# Smart_Garden.net
KiCad netlist of a schematic drawn in EAGLE
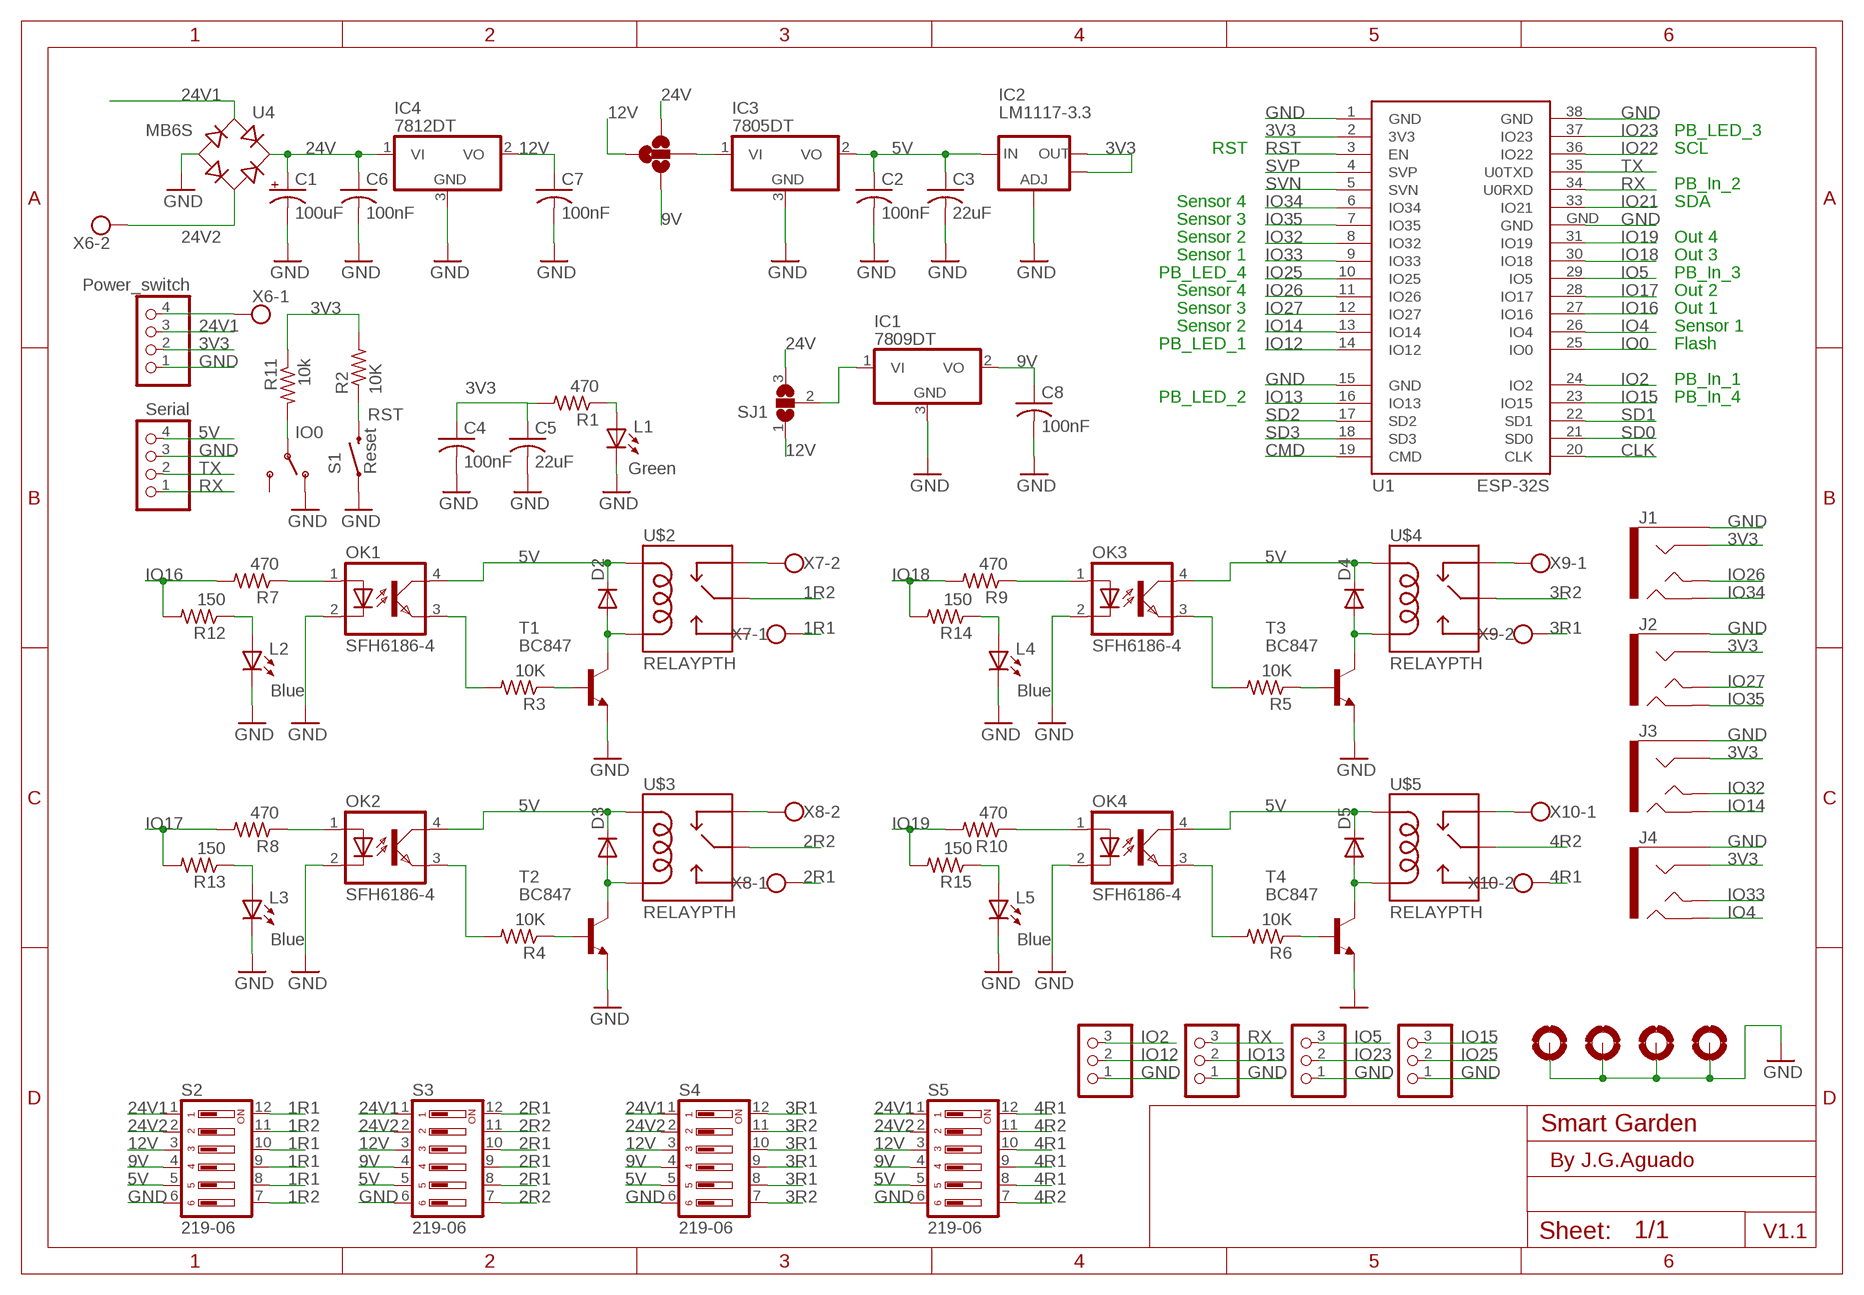
[diagram p0: schematic, sheet 1]

(export (version "E")
  (design (tool "Eeschema 10.0.6"))
  (components
    (comp (ref "C1")
      (value "100uF")
      (footprint "eagle-import:D_7343-31R")
      (libsource (lib "eagle-import") (part "CPOL-USD/7343-31R"))
    )
    (comp (ref "C2")
      (value "100nF")
      (footprint "eagle-import:1206")
      (libsource (lib "eagle-import") (part "C1206"))
    )
    (comp (ref "C3")
      (value "22uF")
      (footprint "eagle-import:1206")
      (libsource (lib "eagle-import") (part "C1206"))
    )
    (comp (ref "C4")
      (value "100nF")
      (footprint "eagle-import:1206")
      (libsource (lib "eagle-import") (part "C1206"))
    )
    (comp (ref "C5")
      (value "22uF")
      (footprint "eagle-import:1206")
      (libsource (lib "eagle-import") (part "C1206"))
    )
    (comp (ref "C6")
      (value "100nF")
      (footprint "eagle-import:1206")
      (libsource (lib "eagle-import") (part "C1206"))
    )
    (comp (ref "C7")
      (value "100nF")
      (footprint "eagle-import:1206")
      (libsource (lib "eagle-import") (part "C1206"))
    )
    (comp (ref "C8")
      (value "100nF")
      (footprint "eagle-import:1206")
      (libsource (lib "eagle-import") (part "C1206"))
    )
    (comp (ref "D2")
      (value "DIODE-SOD123")
      (footprint "eagle-import:SOD123")
      (libsource (lib "eagle-import") (part "DIODE-SOD123"))
    )
    (comp (ref "D3")
      (value "DIODE-SOD123")
      (footprint "eagle-import:SOD123")
      (libsource (lib "eagle-import") (part "DIODE-SOD123"))
    )
    (comp (ref "D4")
      (value "DIODE-SOD123")
      (footprint "eagle-import:SOD123")
      (libsource (lib "eagle-import") (part "DIODE-SOD123"))
    )
    (comp (ref "D5")
      (value "DIODE-SOD123")
      (footprint "eagle-import:SOD123")
      (libsource (lib "eagle-import") (part "DIODE-SOD123"))
    )
    (comp (ref "H1")
      (value "MOUNT-PAD-ROUND3.0")
      (footprint "eagle-import:3,0-PAD")
      (libsource (lib "eagle-import") (part "MOUNT-PAD-ROUND3.0"))
    )
    (comp (ref "H2")
      (value "MOUNT-PAD-ROUND3.0")
      (footprint "eagle-import:3,0-PAD")
      (libsource (lib "eagle-import") (part "MOUNT-PAD-ROUND3.0"))
    )
    (comp (ref "H3")
      (value "MOUNT-PAD-ROUND3.0")
      (footprint "eagle-import:3,0-PAD")
      (libsource (lib "eagle-import") (part "MOUNT-PAD-ROUND3.0"))
    )
    (comp (ref "H4")
      (value "MOUNT-PAD-ROUND3.0")
      (footprint "eagle-import:3,0-PAD")
      (libsource (lib "eagle-import") (part "MOUNT-PAD-ROUND3.0"))
    )
    (comp (ref "IC1")
      (value "7809DT")
      (footprint "eagle-import:TO252")
      (libsource (lib "eagle-import") (part "linear_78DT05"))
    )
    (comp (ref "IC2")
      (value "LM1117-3.3")
      (footprint "eagle-import:SOT223")
      (libsource (lib "eagle-import") (part "V_REG_LM1117SOT223"))
    )
    (comp (ref "IC3")
      (value "7805DT")
      (footprint "eagle-import:TO252")
      (libsource (lib "eagle-import") (part "linear_78DT05"))
    )
    (comp (ref "IC4")
      (value "7812DT")
      (footprint "eagle-import:TO252")
      (libsource (lib "eagle-import") (part "78DT12"))
    )
    (comp (ref "J1")
      (value "AUDIO_JACK_TRRSSMD_RA")
      (footprint "eagle-import:AUDIO_JACK_3.5MM_TRRS_SMD_RA")
      (libsource (lib "eagle-import") (part "AUDIO_JACK_TRRSSMD_RA"))
    )
    (comp (ref "J2")
      (value "AUDIO_JACK_TRRSSMD_RA")
      (footprint "eagle-import:AUDIO_JACK_3.5MM_TRRS_SMD_RA")
      (libsource (lib "eagle-import") (part "AUDIO_JACK_TRRSSMD_RA"))
    )
    (comp (ref "J3")
      (value "AUDIO_JACK_TRRSSMD_RA")
      (footprint "eagle-import:AUDIO_JACK_3.5MM_TRRS_SMD_RA")
      (libsource (lib "eagle-import") (part "AUDIO_JACK_TRRSSMD_RA"))
    )
    (comp (ref "J4")
      (value "AUDIO_JACK_TRRSSMD_RA")
      (footprint "eagle-import:AUDIO_JACK_3.5MM_TRRS_SMD_RA")
      (libsource (lib "eagle-import") (part "AUDIO_JACK_TRRSSMD_RA"))
    )
    (comp (ref "JP1")
      (value "Serial")
      (footprint "eagle-import:1X04")
      (libsource (lib "eagle-import") (part "PINHD-1X4"))
    )
    (comp (ref "JP2")
      (value "PINHD-1X3")
      (footprint "eagle-import:1X03")
      (libsource (lib "eagle-import") (part "PINHD-1X3"))
    )
    (comp (ref "JP3")
      (value "PINHD-1X3")
      (footprint "eagle-import:1X03")
      (libsource (lib "eagle-import") (part "PINHD-1X3"))
    )
    (comp (ref "JP4")
      (value "PINHD-1X3")
      (footprint "eagle-import:1X03")
      (libsource (lib "eagle-import") (part "PINHD-1X3"))
    )
    (comp (ref "JP5")
      (value "PINHD-1X3")
      (footprint "eagle-import:1X03")
      (libsource (lib "eagle-import") (part "PINHD-1X3"))
    )
    (comp (ref "JP6")
      (value "Power_switch")
      (footprint "eagle-import:1X04")
      (libsource (lib "eagle-import") (part "PINHD-1X4"))
    )
    (comp (ref "L1")
      (value "Green")
      (footprint "eagle-import:LED1206")
      (libsource (lib "eagle-import") (part "LED1206"))
    )
    (comp (ref "L2")
      (value "Blue")
      (footprint "eagle-import:LED1206")
      (libsource (lib "eagle-import") (part "LED1206"))
    )
    (comp (ref "L3")
      (value "Blue")
      (footprint "eagle-import:LED1206")
      (libsource (lib "eagle-import") (part "LED1206"))
    )
    (comp (ref "L4")
      (value "Blue")
      (footprint "eagle-import:LED1206")
      (libsource (lib "eagle-import") (part "LED1206"))
    )
    (comp (ref "L5")
      (value "Blue")
      (footprint "eagle-import:LED1206")
      (libsource (lib "eagle-import") (part "LED1206"))
    )
    (comp (ref "OK1")
      (value "SFH6186-4")
      (footprint "eagle-import:SMD4-7")
      (fields (field (name "MF") "VISHAY/TELEFUNKEN"))
      (libsource (lib "eagle-import") (part "SFH618?6-4"))
    )
    (comp (ref "OK2")
      (value "SFH6186-4")
      (footprint "eagle-import:SMD4-7")
      (fields (field (name "MF") "VISHAY/TELEFUNKEN"))
      (libsource (lib "eagle-import") (part "SFH618?6-4"))
    )
    (comp (ref "OK3")
      (value "SFH6186-4")
      (footprint "eagle-import:SMD4-7")
      (fields (field (name "MF") "VISHAY/TELEFUNKEN"))
      (libsource (lib "eagle-import") (part "SFH618?6-4"))
    )
    (comp (ref "OK4")
      (value "SFH6186-4")
      (footprint "eagle-import:SMD4-7")
      (fields (field (name "MF") "VISHAY/TELEFUNKEN"))
      (libsource (lib "eagle-import") (part "SFH618?6-4"))
    )
    (comp (ref "R1")
      (value "470")
      (footprint "eagle-import:1206")
      (libsource (lib "eagle-import") (part "R1206"))
    )
    (comp (ref "R2")
      (value "10K")
      (footprint "eagle-import:R1206")
      (libsource (lib "eagle-import") (part "R-US_R1206"))
    )
    (comp (ref "R3")
      (value "10K")
      (footprint "eagle-import:R1206")
      (libsource (lib "eagle-import") (part "R-US_R1206"))
    )
    (comp (ref "R4")
      (value "10K")
      (footprint "eagle-import:R1206")
      (libsource (lib "eagle-import") (part "R-US_R1206"))
    )
    (comp (ref "R5")
      (value "10K")
      (footprint "eagle-import:R1206")
      (libsource (lib "eagle-import") (part "R-US_R1206"))
    )
    (comp (ref "R6")
      (value "10K")
      (footprint "eagle-import:R1206")
      (libsource (lib "eagle-import") (part "R-US_R1206"))
    )
    (comp (ref "R7")
      (value "470")
      (footprint "eagle-import:R1206")
      (libsource (lib "eagle-import") (part "R-US_R1206"))
    )
    (comp (ref "R8")
      (value "470")
      (footprint "eagle-import:R1206")
      (libsource (lib "eagle-import") (part "R-US_R1206"))
    )
    (comp (ref "R9")
      (value "470")
      (footprint "eagle-import:R1206")
      (libsource (lib "eagle-import") (part "R-US_R1206"))
    )
    (comp (ref "R10")
      (value "470")
      (footprint "eagle-import:R1206")
      (libsource (lib "eagle-import") (part "R-US_R1206"))
    )
    (comp (ref "R11")
      (value "10k")
      (footprint "eagle-import:1206")
      (libsource (lib "eagle-import") (part "R1206"))
    )
    (comp (ref "R12")
      (value "150")
      (footprint "eagle-import:1206")
      (libsource (lib "eagle-import") (part "R1206"))
    )
    (comp (ref "R13")
      (value "150")
      (footprint "eagle-import:1206")
      (libsource (lib "eagle-import") (part "R1206"))
    )
    (comp (ref "R14")
      (value "150")
      (footprint "eagle-import:1206")
      (libsource (lib "eagle-import") (part "R1206"))
    )
    (comp (ref "R15")
      (value "150")
      (footprint "eagle-import:1206")
      (libsource (lib "eagle-import") (part "R1206"))
    )
    (comp (ref "S1")
      (value "Reset")
      (footprint "eagle-import:TACTILE_SWITCH_TALL")
      (libsource (lib "eagle-import") (part "SWITCH-MOMENTARY-2SMD-4"))
    )
    (comp (ref "S2")
      (value "219-06")
      (footprint "eagle-import:CTS-219-06")
      (libsource (lib "eagle-import") (part "219-06"))
    )
    (comp (ref "S3")
      (value "219-06")
      (footprint "eagle-import:CTS-219-06")
      (libsource (lib "eagle-import") (part "219-06"))
    )
    (comp (ref "S4")
      (value "219-06")
      (footprint "eagle-import:CTS-219-06")
      (libsource (lib "eagle-import") (part "219-06"))
    )
    (comp (ref "S5")
      (value "219-06")
      (footprint "eagle-import:CTS-219-06")
      (libsource (lib "eagle-import") (part "219-06"))
    )
    (comp (ref "SJ1")
      (value "SJ2W")
      (footprint "eagle-import:SJ_2")
      (libsource (lib "eagle-import") (part "SJ2W"))
    )
    (comp (ref "SJ2")
      (value "SJ3W")
      (footprint "eagle-import:SJ_3_R")
      (libsource (lib "eagle-import") (part "SJ3W"))
    )
    (comp (ref "T1")
      (value "BC847")
      (footprint "eagle-import:SOT23")
      (libsource (lib "eagle-import") (part "BC847"))
    )
    (comp (ref "T2")
      (value "BC847")
      (footprint "eagle-import:SOT23")
      (libsource (lib "eagle-import") (part "BC847"))
    )
    (comp (ref "T3")
      (value "BC847")
      (footprint "eagle-import:SOT23")
      (libsource (lib "eagle-import") (part "BC847"))
    )
    (comp (ref "T4")
      (value "BC847")
      (footprint "eagle-import:SOT23")
      (libsource (lib "eagle-import") (part "BC847"))
    )
    (comp (ref "U$2")
      (value "RELAYPTH")
      (footprint "eagle-import:SRD-05VDC-SL-C")
      (libsource (lib "eagle-import") (part "RELAYPTH"))
    )
    (comp (ref "U$3")
      (value "RELAYPTH")
      (footprint "eagle-import:SRD-05VDC-SL-C")
      (libsource (lib "eagle-import") (part "RELAYPTH"))
    )
    (comp (ref "U$4")
      (value "RELAYPTH")
      (footprint "eagle-import:SRD-05VDC-SL-C")
      (libsource (lib "eagle-import") (part "RELAYPTH"))
    )
    (comp (ref "U$5")
      (value "RELAYPTH")
      (footprint "eagle-import:SRD-05VDC-SL-C")
      (libsource (lib "eagle-import") (part "RELAYPTH"))
    )
    (comp (ref "U$6")
      (value "SWITCH_SPDT")
      (footprint "eagle-import:KPS-1290")
      (libsource (lib "eagle-import") (part "SWITCH_SPDT"))
    )
    (comp (ref "U1")
      (value "ESP-32S")
      (footprint "eagle-import:ESP-32S")
      (libsource (lib "eagle-import") (part "ESP-32S"))
    )
    (comp (ref "U4")
      (value "MB6S")
      (footprint "eagle-import:SOIC-4")
      (libsource (lib "eagle-import") (part "MBS6"))
    )
    (comp (ref "X6")
      (value "W237-102")
      (footprint "eagle-import:W237-102")
      (fields (field (name "MPN") "237-102"))
      (libsource (lib "eagle-import") (part "W237-102"))
    )
    (comp (ref "X7")
      (value "W237-102")
      (footprint "eagle-import:W237-102")
      (fields (field (name "MPN") "237-102"))
      (libsource (lib "eagle-import") (part "W237-102"))
    )
    (comp (ref "X8")
      (value "W237-102")
      (footprint "eagle-import:W237-102")
      (fields (field (name "MPN") "237-102"))
      (libsource (lib "eagle-import") (part "W237-102"))
    )
    (comp (ref "X9")
      (value "W237-102")
      (footprint "eagle-import:W237-102")
      (fields (field (name "MPN") "237-102"))
      (libsource (lib "eagle-import") (part "W237-102"))
    )
    (comp (ref "X10")
      (value "W237-102")
      (footprint "eagle-import:W237-102")
      (fields (field (name "MPN") "237-102"))
      (libsource (lib "eagle-import") (part "W237-102"))
    )
  )
  (nets
    (net (code "1") (name "/1R1") (class "Default")
      (node (ref "S2") (pin "10") (pinfunction "10_10") (pintype "passive"))
      (node (ref "S2") (pin "12") (pinfunction "12_12") (pintype "passive"))
      (node (ref "S2") (pin "8") (pinfunction "8_8") (pintype "passive"))
      (node (ref "S2") (pin "9") (pinfunction "9_9") (pintype "passive"))
      (node (ref "X7") (pin "1") (pinfunction "KL_1") (pintype "passive"))
    )
    (net (code "2") (name "/1R2") (class "Default")
      (node (ref "S2") (pin "11") (pinfunction "11_11") (pintype "passive"))
      (node (ref "S2") (pin "7") (pinfunction "7_7") (pintype "passive"))
      (node (ref "U$2") (pin "SWCOMMON") (pinfunction "SWCOMMON_SWCOMMON") (pintype "bidirectional"))
    )
    (net (code "3") (name "/2R1") (class "Default")
      (node (ref "S3") (pin "10") (pinfunction "10_10") (pintype "passive"))
      (node (ref "S3") (pin "12") (pinfunction "12_12") (pintype "passive"))
      (node (ref "S3") (pin "8") (pinfunction "8_8") (pintype "passive"))
      (node (ref "S3") (pin "9") (pinfunction "9_9") (pintype "passive"))
      (node (ref "X8") (pin "1") (pinfunction "KL_1") (pintype "passive"))
    )
    (net (code "4") (name "/2R2") (class "Default")
      (node (ref "S3") (pin "11") (pinfunction "11_11") (pintype "passive"))
      (node (ref "S3") (pin "7") (pinfunction "7_7") (pintype "passive"))
      (node (ref "U$3") (pin "SWCOMMON") (pinfunction "SWCOMMON_SWCOMMON") (pintype "bidirectional"))
    )
    (net (code "5") (name "/3R1") (class "Default")
      (node (ref "S4") (pin "10") (pinfunction "10_10") (pintype "passive"))
      (node (ref "S4") (pin "12") (pinfunction "12_12") (pintype "passive"))
      (node (ref "S4") (pin "8") (pinfunction "8_8") (pintype "passive"))
      (node (ref "S4") (pin "9") (pinfunction "9_9") (pintype "passive"))
      (node (ref "X9") (pin "2") (pinfunction "KL_2") (pintype "passive"))
    )
    (net (code "6") (name "/3R2") (class "Default")
      (node (ref "S4") (pin "11") (pinfunction "11_11") (pintype "passive"))
      (node (ref "S4") (pin "7") (pinfunction "7_7") (pintype "passive"))
      (node (ref "U$4") (pin "SWCOMMON") (pinfunction "SWCOMMON_SWCOMMON") (pintype "bidirectional"))
    )
    (net (code "7") (name "/3V3") (class "Default")
      (node (ref "C4") (pin "1") (pinfunction "1_1") (pintype "passive"))
      (node (ref "C5") (pin "1") (pinfunction "1_1") (pintype "passive"))
      (node (ref "IC2") (pin "2") (pinfunction "OUT_2") (pintype "output"))
      (node (ref "IC2") (pin "4") (pinfunction "OUT_4") (pintype "output"))
      (node (ref "J1") (pin "RING1") (pinfunction "RING1_RING1") (pintype "bidirectional"))
      (node (ref "J2") (pin "RING1") (pinfunction "RING1_RING1") (pintype "bidirectional"))
      (node (ref "J3") (pin "RING1") (pinfunction "RING1_RING1") (pintype "bidirectional"))
      (node (ref "J4") (pin "RING1") (pinfunction "RING1_RING1") (pintype "bidirectional"))
      (node (ref "JP6") (pin "2") (pinfunction "2_2") (pintype "passive"))
      (node (ref "R1") (pin "2") (pinfunction "2_2") (pintype "passive"))
      (node (ref "R11") (pin "1") (pinfunction "1_1") (pintype "passive"))
      (node (ref "R2") (pin "2") (pinfunction "2_2") (pintype "passive"))
      (node (ref "U1") (pin "2") (pinfunction "3V3_2") (pintype "power_in"))
    )
    (net (code "8") (name "/4R1") (class "Default")
      (node (ref "S5") (pin "10") (pinfunction "10_10") (pintype "passive"))
      (node (ref "S5") (pin "12") (pinfunction "12_12") (pintype "passive"))
      (node (ref "S5") (pin "8") (pinfunction "8_8") (pintype "passive"))
      (node (ref "S5") (pin "9") (pinfunction "9_9") (pintype "passive"))
      (node (ref "X10") (pin "2") (pinfunction "KL_2") (pintype "passive"))
    )
    (net (code "9") (name "/4R2") (class "Default")
      (node (ref "S5") (pin "11") (pinfunction "11_11") (pintype "passive"))
      (node (ref "S5") (pin "7") (pinfunction "7_7") (pintype "passive"))
      (node (ref "U$5") (pin "SWCOMMON") (pinfunction "SWCOMMON_SWCOMMON") (pintype "bidirectional"))
    )
    (net (code "10") (name "/5V") (class "Default")
      (node (ref "C2") (pin "1") (pinfunction "1_1") (pintype "passive"))
      (node (ref "C3") (pin "1") (pinfunction "1_1") (pintype "passive"))
      (node (ref "D2") (pin "C") (pinfunction "C_C") (pintype "passive"))
      (node (ref "D3") (pin "C") (pinfunction "C_C") (pintype "passive"))
      (node (ref "D4") (pin "C") (pinfunction "C_C") (pintype "passive"))
      (node (ref "D5") (pin "C") (pinfunction "C_C") (pintype "passive"))
      (node (ref "IC2") (pin "3") (pinfunction "IN_3") (pintype "input"))
      (node (ref "IC3") (pin "2") (pinfunction "VO_2") (pintype "passive"))
      (node (ref "JP1") (pin "4") (pinfunction "4_4") (pintype "passive"))
      (node (ref "OK1") (pin "4") (pinfunction "COL_4") (pintype "passive"))
      (node (ref "OK2") (pin "4") (pinfunction "COL_4") (pintype "passive"))
      (node (ref "OK3") (pin "4") (pinfunction "COL_4") (pintype "passive"))
      (node (ref "OK4") (pin "4") (pinfunction "COL_4") (pintype "passive"))
      (node (ref "S2") (pin "5") (pinfunction "5_5") (pintype "passive"))
      (node (ref "S3") (pin "5") (pinfunction "5_5") (pintype "passive"))
      (node (ref "S4") (pin "5") (pinfunction "5_5") (pintype "passive"))
      (node (ref "S5") (pin "5") (pinfunction "5_5") (pintype "passive"))
      (node (ref "U$2") (pin "COIL1") (pinfunction "COIL1_COIL1") (pintype "bidirectional"))
      (node (ref "U$3") (pin "COIL1") (pinfunction "COIL1_COIL1") (pintype "bidirectional"))
      (node (ref "U$4") (pin "COIL1") (pinfunction "COIL1_COIL1") (pintype "bidirectional"))
      (node (ref "U$5") (pin "COIL1") (pinfunction "COIL1_COIL1") (pintype "bidirectional"))
    )
    (net (code "11") (name "/9V") (class "Default")
      (node (ref "C8") (pin "1") (pinfunction "1_1") (pintype "passive"))
      (node (ref "IC1") (pin "2") (pinfunction "VO_2") (pintype "passive"))
      (node (ref "S2") (pin "4") (pinfunction "4_4") (pintype "passive"))
      (node (ref "S3") (pin "4") (pinfunction "4_4") (pintype "passive"))
      (node (ref "S4") (pin "4") (pinfunction "4_4") (pintype "passive"))
      (node (ref "S5") (pin "4") (pinfunction "4_4") (pintype "passive"))
      (node (ref "SJ2") (pin "P$2") (pinfunction "2_P$2") (pintype "passive"))
    )
    (net (code "12") (name "/12V") (class "Default")
      (node (ref "C7") (pin "1") (pinfunction "1_1") (pintype "passive"))
      (node (ref "IC4") (pin "2") (pinfunction "VO_2") (pintype "passive"))
      (node (ref "S2") (pin "3") (pinfunction "3_3") (pintype "passive"))
      (node (ref "S3") (pin "3") (pinfunction "3_3") (pintype "passive"))
      (node (ref "S4") (pin "3") (pinfunction "3_3") (pintype "passive"))
      (node (ref "S5") (pin "3") (pinfunction "3_3") (pintype "passive"))
      (node (ref "SJ1") (pin "1") (pinfunction "1_1") (pintype "passive"))
      (node (ref "SJ2") (pin "P$4") (pinfunction "4_P$4") (pintype "passive"))
    )
    (net (code "13") (name "/24V") (class "Default")
      (node (ref "C1") (pin "+") (pinfunction "+_+") (pintype "passive"))
      (node (ref "C6") (pin "1") (pinfunction "1_1") (pintype "passive"))
      (node (ref "IC4") (pin "1") (pinfunction "VI_1") (pintype "input"))
      (node (ref "SJ1") (pin "3") (pinfunction "3_3") (pintype "passive"))
      (node (ref "SJ2") (pin "P$3") (pinfunction "3_P$3") (pintype "passive"))
      (node (ref "U4") (pin "+") (pinfunction "+_+") (pintype "passive"))
    )
    (net (code "14") (name "/24V1") (class "Default")
      (node (ref "JP6") (pin "3") (pinfunction "3_3") (pintype "passive"))
      (node (ref "S2") (pin "1") (pinfunction "1_1") (pintype "passive"))
      (node (ref "S3") (pin "1") (pinfunction "1_1") (pintype "passive"))
      (node (ref "S4") (pin "1") (pinfunction "1_1") (pintype "passive"))
      (node (ref "S5") (pin "1") (pinfunction "1_1") (pintype "passive"))
      (node (ref "U4") (pin "~1") (pinfunction "AC1_~1") (pintype "passive"))
    )
    (net (code "15") (name "/24V2") (class "Default")
      (node (ref "S2") (pin "2") (pinfunction "2_2") (pintype "passive"))
      (node (ref "S3") (pin "2") (pinfunction "2_2") (pintype "passive"))
      (node (ref "S4") (pin "2") (pinfunction "2_2") (pintype "passive"))
      (node (ref "S5") (pin "2") (pinfunction "2_2") (pintype "passive"))
      (node (ref "U4") (pin "~2") (pinfunction "AC2_~2") (pintype "passive"))
      (node (ref "X6") (pin "2") (pinfunction "KL_2") (pintype "passive"))
    )
    (net (code "16") (name "/CLK") (class "Default")
      (node (ref "U1") (pin "20") (pinfunction "CLK_20") (pintype "bidirectional"))
    )
    (net (code "17") (name "/CMD") (class "Default")
      (node (ref "U1") (pin "19") (pinfunction "CMD_19") (pintype "bidirectional"))
    )
    (net (code "18") (name "/IO0") (class "Default")
      (node (ref "R11") (pin "2") (pinfunction "2_2") (pintype "passive"))
      (node (ref "U$6") (pin "P") (pinfunction "P_P") (pintype "passive"))
      (node (ref "U1") (pin "25") (pinfunction "IO0_25") (pintype "bidirectional"))
    )
    (net (code "19") (name "/IO2") (class "Default")
      (node (ref "JP2") (pin "3") (pinfunction "3_3") (pintype "passive"))
      (node (ref "U1") (pin "24") (pinfunction "IO2_24") (pintype "bidirectional"))
    )
    (net (code "20") (name "/IO4") (class "Default")
      (node (ref "J4") (pin "RING2") (pinfunction "RING2_RING2") (pintype "bidirectional"))
      (node (ref "U1") (pin "26") (pinfunction "IO4_26") (pintype "bidirectional"))
    )
    (net (code "21") (name "/IO5") (class "Default")
      (node (ref "JP4") (pin "3") (pinfunction "3_3") (pintype "passive"))
      (node (ref "U1") (pin "29") (pinfunction "IO5_29") (pintype "bidirectional"))
    )
    (net (code "22") (name "/IO12") (class "Default")
      (node (ref "JP2") (pin "2") (pinfunction "2_2") (pintype "passive"))
      (node (ref "U1") (pin "14") (pinfunction "IO12_14") (pintype "bidirectional"))
    )
    (net (code "23") (name "/IO13") (class "Default")
      (node (ref "JP3") (pin "2") (pinfunction "2_2") (pintype "passive"))
      (node (ref "U1") (pin "16") (pinfunction "IO13_16") (pintype "bidirectional"))
    )
    (net (code "24") (name "/IO14") (class "Default")
      (node (ref "J3") (pin "RING2") (pinfunction "RING2_RING2") (pintype "bidirectional"))
      (node (ref "U1") (pin "13") (pinfunction "IO14_13") (pintype "bidirectional"))
    )
    (net (code "25") (name "/IO15") (class "Default")
      (node (ref "JP5") (pin "3") (pinfunction "3_3") (pintype "passive"))
      (node (ref "U1") (pin "23") (pinfunction "IO15_23") (pintype "bidirectional"))
    )
    (net (code "26") (name "/IO16") (class "Default")
      (node (ref "R12") (pin "2") (pinfunction "2_2") (pintype "passive"))
      (node (ref "R7") (pin "2") (pinfunction "2_2") (pintype "passive"))
      (node (ref "U1") (pin "27") (pinfunction "IO16_27") (pintype "bidirectional"))
    )
    (net (code "27") (name "/IO17") (class "Default")
      (node (ref "R13") (pin "2") (pinfunction "2_2") (pintype "passive"))
      (node (ref "R8") (pin "2") (pinfunction "2_2") (pintype "passive"))
      (node (ref "U1") (pin "28") (pinfunction "IO17_28") (pintype "bidirectional"))
    )
    (net (code "28") (name "/IO18") (class "Default")
      (node (ref "R14") (pin "2") (pinfunction "2_2") (pintype "passive"))
      (node (ref "R9") (pin "2") (pinfunction "2_2") (pintype "passive"))
      (node (ref "U1") (pin "30") (pinfunction "IO18_30") (pintype "bidirectional"))
    )
    (net (code "29") (name "/IO19") (class "Default")
      (node (ref "R10") (pin "2") (pinfunction "2_2") (pintype "passive"))
      (node (ref "R15") (pin "2") (pinfunction "2_2") (pintype "passive"))
      (node (ref "U1") (pin "31") (pinfunction "IO19_31") (pintype "bidirectional"))
    )
    (net (code "30") (name "/IO21") (class "Default")
      (node (ref "U1") (pin "33") (pinfunction "IO21_33") (pintype "bidirectional"))
    )
    (net (code "31") (name "/IO22") (class "Default")
      (node (ref "U1") (pin "36") (pinfunction "IO22_36") (pintype "bidirectional"))
    )
    (net (code "32") (name "/IO23") (class "Default")
      (node (ref "JP4") (pin "2") (pinfunction "2_2") (pintype "passive"))
      (node (ref "U1") (pin "37") (pinfunction "IO23_37") (pintype "bidirectional"))
    )
    (net (code "33") (name "/IO25") (class "Default")
      (node (ref "JP5") (pin "2") (pinfunction "2_2") (pintype "passive"))
      (node (ref "U1") (pin "10") (pinfunction "IO25_10") (pintype "bidirectional"))
    )
    (net (code "34") (name "/IO26") (class "Default")
      (node (ref "J1") (pin "TIP") (pinfunction "TIP_TIP") (pintype "bidirectional"))
      (node (ref "U1") (pin "11") (pinfunction "IO26_11") (pintype "bidirectional"))
    )
    (net (code "35") (name "/IO27") (class "Default")
      (node (ref "J2") (pin "TIP") (pinfunction "TIP_TIP") (pintype "bidirectional"))
      (node (ref "U1") (pin "12") (pinfunction "IO27_12") (pintype "bidirectional"))
    )
    (net (code "36") (name "/IO32") (class "Default")
      (node (ref "J3") (pin "TIP") (pinfunction "TIP_TIP") (pintype "bidirectional"))
      (node (ref "U1") (pin "8") (pinfunction "IO32_8") (pintype "bidirectional"))
    )
    (net (code "37") (name "/IO33") (class "Default")
      (node (ref "J4") (pin "TIP") (pinfunction "TIP_TIP") (pintype "bidirectional"))
      (node (ref "U1") (pin "9") (pinfunction "IO33_9") (pintype "bidirectional"))
    )
    (net (code "38") (name "/IO34") (class "Default")
      (node (ref "J1") (pin "RING2") (pinfunction "RING2_RING2") (pintype "bidirectional"))
      (node (ref "U1") (pin "6") (pinfunction "IO34_6") (pintype "bidirectional"))
    )
    (net (code "39") (name "/IO35") (class "Default")
      (node (ref "J2") (pin "RING2") (pinfunction "RING2_RING2") (pintype "bidirectional"))
      (node (ref "U1") (pin "7") (pinfunction "IO35_7") (pintype "bidirectional"))
    )
    (net (code "40") (name "/RST") (class "Default")
      (node (ref "R2") (pin "1") (pinfunction "1_1") (pintype "passive"))
      (node (ref "S1") (pin "B2") (pinfunction "2_B2") (pintype "passive"))
      (node (ref "U1") (pin "3") (pinfunction "EN_3") (pintype "input"))
    )
    (net (code "41") (name "/RX") (class "Default")
      (node (ref "JP1") (pin "1") (pinfunction "1_1") (pintype "passive"))
      (node (ref "JP3") (pin "3") (pinfunction "3_3") (pintype "passive"))
      (node (ref "U1") (pin "34") (pinfunction "U0RXD_34") (pintype "bidirectional"))
    )
    (net (code "42") (name "/SD0") (class "Default")
      (node (ref "U1") (pin "21") (pinfunction "SD0_21") (pintype "bidirectional"))
    )
    (net (code "43") (name "/SD1") (class "Default")
      (node (ref "U1") (pin "22") (pinfunction "SD1_22") (pintype "bidirectional"))
    )
    (net (code "44") (name "/SD2") (class "Default")
      (node (ref "U1") (pin "17") (pinfunction "SD2_17") (pintype "bidirectional"))
    )
    (net (code "45") (name "/SD3") (class "Default")
      (node (ref "U1") (pin "18") (pinfunction "SD3_18") (pintype "bidirectional"))
    )
    (net (code "46") (name "/SVN") (class "Default")
      (node (ref "U1") (pin "5") (pinfunction "SVN_5") (pintype "bidirectional"))
    )
    (net (code "47") (name "/SVP") (class "Default")
      (node (ref "U1") (pin "4") (pinfunction "SVP_4") (pintype "bidirectional"))
    )
    (net (code "48") (name "/TX") (class "Default")
      (node (ref "JP1") (pin "2") (pinfunction "2_2") (pintype "passive"))
      (node (ref "U1") (pin "35") (pinfunction "U0TXD_35") (pintype "bidirectional"))
    )
    (net (code "49") (name "GND") (class "Default")
      (node (ref "C1") (pin "-") (pinfunction "-_-") (pintype "passive"))
      (node (ref "C2") (pin "2") (pinfunction "2_2") (pintype "passive"))
      (node (ref "C3") (pin "2") (pinfunction "2_2") (pintype "passive"))
      (node (ref "C4") (pin "2") (pinfunction "2_2") (pintype "passive"))
      (node (ref "C5") (pin "2") (pinfunction "2_2") (pintype "passive"))
      (node (ref "C6") (pin "2") (pinfunction "2_2") (pintype "passive"))
      (node (ref "C7") (pin "2") (pinfunction "2_2") (pintype "passive"))
      (node (ref "C8") (pin "2") (pinfunction "2_2") (pintype "passive"))
      (node (ref "H1") (pin "B3,0") (pinfunction "MOUNT_B3,0") (pintype "passive"))
      (node (ref "H2") (pin "B3,0") (pinfunction "MOUNT_B3,0") (pintype "passive"))
      (node (ref "H3") (pin "B3,0") (pinfunction "MOUNT_B3,0") (pintype "passive"))
      (node (ref "H4") (pin "B3,0") (pinfunction "MOUNT_B3,0") (pintype "passive"))
      (node (ref "IC1") (pin "3") (pinfunction "GND_3") (pintype "passive"))
      (node (ref "IC2") (pin "1") (pinfunction "ADJ_1") (pintype "input"))
      (node (ref "IC3") (pin "3") (pinfunction "GND_3") (pintype "passive"))
      (node (ref "IC4") (pin "3") (pinfunction "GND_3") (pintype "passive"))
      (node (ref "J1") (pin "EARTH") (pinfunction "EARTH_EARTH") (pintype "bidirectional"))
      (node (ref "J2") (pin "EARTH") (pinfunction "EARTH_EARTH") (pintype "bidirectional"))
      (node (ref "J3") (pin "EARTH") (pinfunction "EARTH_EARTH") (pintype "bidirectional"))
      (node (ref "J4") (pin "EARTH") (pinfunction "EARTH_EARTH") (pintype "bidirectional"))
      (node (ref "JP1") (pin "3") (pinfunction "3_3") (pintype "passive"))
      (node (ref "JP2") (pin "1") (pinfunction "1_1") (pintype "passive"))
      (node (ref "JP3") (pin "1") (pinfunction "1_1") (pintype "passive"))
      (node (ref "JP4") (pin "1") (pinfunction "1_1") (pintype "passive"))
      (node (ref "JP5") (pin "1") (pinfunction "1_1") (pintype "passive"))
      (node (ref "JP6") (pin "1") (pinfunction "1_1") (pintype "passive"))
      (node (ref "L1") (pin "C") (pinfunction "C_C") (pintype "passive"))
      (node (ref "L2") (pin "C") (pinfunction "C_C") (pintype "passive"))
      (node (ref "L3") (pin "C") (pinfunction "C_C") (pintype "passive"))
      (node (ref "L4") (pin "C") (pinfunction "C_C") (pintype "passive"))
      (node (ref "L5") (pin "C") (pinfunction "C_C") (pintype "passive"))
      (node (ref "OK1") (pin "2") (pinfunction "C_2") (pintype "passive"))
      (node (ref "OK2") (pin "2") (pinfunction "C_2") (pintype "passive"))
      (node (ref "OK3") (pin "2") (pinfunction "C_2") (pintype "passive"))
      (node (ref "OK4") (pin "2") (pinfunction "C_2") (pintype "passive"))
      (node (ref "S1") (pin "A2") (pinfunction "1_A2") (pintype "passive"))
      (node (ref "S2") (pin "6") (pinfunction "6_6") (pintype "passive"))
      (node (ref "S3") (pin "6") (pinfunction "6_6") (pintype "passive"))
      (node (ref "S4") (pin "6") (pinfunction "6_6") (pintype "passive"))
      (node (ref "S5") (pin "6") (pinfunction "6_6") (pintype "passive"))
      (node (ref "T1") (pin "2") (pinfunction "E_2") (pintype "passive"))
      (node (ref "T2") (pin "2") (pinfunction "E_2") (pintype "passive"))
      (node (ref "T3") (pin "2") (pinfunction "E_2") (pintype "passive"))
      (node (ref "T4") (pin "2") (pinfunction "E_2") (pintype "passive"))
      (node (ref "U$6") (pin "O") (pinfunction "O_O") (pintype "passive"))
      (node (ref "U1") (pin "1") (pinfunction "GND_1") (pintype "power_in"))
      (node (ref "U1") (pin "15") (pinfunction "GND_15") (pintype "power_in"))
      (node (ref "U1") (pin "38") (pinfunction "GND_38") (pintype "power_in"))
      (node (ref "U1") (pin "GND") (pinfunction "GND_GND") (pintype "power_in"))
      (node (ref "U4") (pin "-") (pinfunction "-_-") (pintype "passive"))
    )
    (net (code "50") (name "Net-(IC1-VI)") (class "Default")
      (node (ref "IC1") (pin "1") (pinfunction "VI_1") (pintype "input"))
      (node (ref "SJ1") (pin "2") (pinfunction "2_2") (pintype "passive"))
    )
    (net (code "51") (name "Net-(IC3-VI)") (class "Default")
      (node (ref "IC3") (pin "1") (pinfunction "VI_1") (pintype "input"))
      (node (ref "SJ2") (pin "P$1") (pinfunction "1_P$1") (pintype "passive"))
    )
    (net (code "52") (name "Net-(L1-PadA)") (class "Default")
      (node (ref "L1") (pin "A") (pinfunction "A_A") (pintype "passive"))
      (node (ref "R1") (pin "1") (pinfunction "1_1") (pintype "passive"))
    )
    (net (code "53") (name "Net-(L2-PadA)") (class "Default")
      (node (ref "L2") (pin "A") (pinfunction "A_A") (pintype "passive"))
      (node (ref "R12") (pin "1") (pinfunction "1_1") (pintype "passive"))
    )
    (net (code "54") (name "Net-(L3-PadA)") (class "Default")
      (node (ref "L3") (pin "A") (pinfunction "A_A") (pintype "passive"))
      (node (ref "R13") (pin "1") (pinfunction "1_1") (pintype "passive"))
    )
    (net (code "55") (name "Net-(L4-PadA)") (class "Default")
      (node (ref "L4") (pin "A") (pinfunction "A_A") (pintype "passive"))
      (node (ref "R14") (pin "1") (pinfunction "1_1") (pintype "passive"))
    )
    (net (code "56") (name "Net-(L5-PadA)") (class "Default")
      (node (ref "L5") (pin "A") (pinfunction "A_A") (pintype "passive"))
      (node (ref "R15") (pin "1") (pinfunction "1_1") (pintype "passive"))
    )
    (net (code "57") (name "Net-(OK1-A)") (class "Default")
      (node (ref "OK1") (pin "1") (pinfunction "A_1") (pintype "passive"))
      (node (ref "R7") (pin "1") (pinfunction "1_1") (pintype "passive"))
    )
    (net (code "58") (name "Net-(OK1-EMIT)") (class "Default")
      (node (ref "OK1") (pin "3") (pinfunction "EMIT_3") (pintype "passive"))
      (node (ref "R3") (pin "2") (pinfunction "2_2") (pintype "passive"))
    )
    (net (code "59") (name "Net-(OK2-A)") (class "Default")
      (node (ref "OK2") (pin "1") (pinfunction "A_1") (pintype "passive"))
      (node (ref "R8") (pin "1") (pinfunction "1_1") (pintype "passive"))
    )
    (net (code "60") (name "Net-(OK2-EMIT)") (class "Default")
      (node (ref "OK2") (pin "3") (pinfunction "EMIT_3") (pintype "passive"))
      (node (ref "R4") (pin "2") (pinfunction "2_2") (pintype "passive"))
    )
    (net (code "61") (name "Net-(OK3-A)") (class "Default")
      (node (ref "OK3") (pin "1") (pinfunction "A_1") (pintype "passive"))
      (node (ref "R9") (pin "1") (pinfunction "1_1") (pintype "passive"))
    )
    (net (code "62") (name "Net-(OK3-EMIT)") (class "Default")
      (node (ref "OK3") (pin "3") (pinfunction "EMIT_3") (pintype "passive"))
      (node (ref "R5") (pin "2") (pinfunction "2_2") (pintype "passive"))
    )
    (net (code "63") (name "Net-(OK4-A)") (class "Default")
      (node (ref "OK4") (pin "1") (pinfunction "A_1") (pintype "passive"))
      (node (ref "R10") (pin "1") (pinfunction "1_1") (pintype "passive"))
    )
    (net (code "64") (name "Net-(OK4-EMIT)") (class "Default")
      (node (ref "OK4") (pin "3") (pinfunction "EMIT_3") (pintype "passive"))
      (node (ref "R6") (pin "2") (pinfunction "2_2") (pintype "passive"))
    )
    (net (code "65") (name "Net-(T1-B)") (class "Default")
      (node (ref "R3") (pin "1") (pinfunction "1_1") (pintype "passive"))
      (node (ref "T1") (pin "1") (pinfunction "B_1") (pintype "passive"))
    )
    (net (code "66") (name "Net-(T1-C)") (class "Default")
      (node (ref "D2") (pin "A") (pinfunction "A_A") (pintype "passive"))
      (node (ref "T1") (pin "3") (pinfunction "C_3") (pintype "passive"))
      (node (ref "U$2") (pin "COIL0") (pinfunction "COIL0_COIL0") (pintype "bidirectional"))
    )
    (net (code "67") (name "Net-(T2-B)") (class "Default")
      (node (ref "R4") (pin "1") (pinfunction "1_1") (pintype "passive"))
      (node (ref "T2") (pin "1") (pinfunction "B_1") (pintype "passive"))
    )
    (net (code "68") (name "Net-(T2-C)") (class "Default")
      (node (ref "D3") (pin "A") (pinfunction "A_A") (pintype "passive"))
      (node (ref "T2") (pin "3") (pinfunction "C_3") (pintype "passive"))
      (node (ref "U$3") (pin "COIL0") (pinfunction "COIL0_COIL0") (pintype "bidirectional"))
    )
    (net (code "69") (name "Net-(T3-B)") (class "Default")
      (node (ref "R5") (pin "1") (pinfunction "1_1") (pintype "passive"))
      (node (ref "T3") (pin "1") (pinfunction "B_1") (pintype "passive"))
    )
    (net (code "70") (name "Net-(T3-C)") (class "Default")
      (node (ref "D4") (pin "A") (pinfunction "A_A") (pintype "passive"))
      (node (ref "T3") (pin "3") (pinfunction "C_3") (pintype "passive"))
      (node (ref "U$4") (pin "COIL0") (pinfunction "COIL0_COIL0") (pintype "bidirectional"))
    )
    (net (code "71") (name "Net-(T4-B)") (class "Default")
      (node (ref "R6") (pin "1") (pinfunction "1_1") (pintype "passive"))
      (node (ref "T4") (pin "1") (pinfunction "B_1") (pintype "passive"))
    )
    (net (code "72") (name "Net-(T4-C)") (class "Default")
      (node (ref "D5") (pin "A") (pinfunction "A_A") (pintype "passive"))
      (node (ref "T4") (pin "3") (pinfunction "C_3") (pintype "passive"))
      (node (ref "U$5") (pin "COIL0") (pinfunction "COIL0_COIL0") (pintype "bidirectional"))
    )
    (net (code "73") (name "Net-(U$2-SWCLOSE)") (class "Default")
      (node (ref "U$2") (pin "SWCLOSED") (pinfunction "SWCLOSE_SWCLOSED") (pintype "bidirectional"))
      (node (ref "X7") (pin "2") (pinfunction "KL_2") (pintype "passive"))
    )
    (net (code "74") (name "Net-(U$3-SWCLOSE)") (class "Default")
      (node (ref "U$3") (pin "SWCLOSED") (pinfunction "SWCLOSE_SWCLOSED") (pintype "bidirectional"))
      (node (ref "X8") (pin "2") (pinfunction "KL_2") (pintype "passive"))
    )
    (net (code "75") (name "Net-(U$4-SWCLOSE)") (class "Default")
      (node (ref "U$4") (pin "SWCLOSED") (pinfunction "SWCLOSE_SWCLOSED") (pintype "bidirectional"))
      (node (ref "X9") (pin "1") (pinfunction "KL_1") (pintype "passive"))
    )
    (net (code "76") (name "Net-(U$5-SWCLOSE)") (class "Default")
      (node (ref "U$5") (pin "SWCLOSED") (pinfunction "SWCLOSE_SWCLOSED") (pintype "bidirectional"))
      (node (ref "X10") (pin "1") (pinfunction "KL_1") (pintype "passive"))
    )
    (net (code "77") (name "Net-(X6A-KL)") (class "Default")
      (node (ref "JP6") (pin "4") (pinfunction "4_4") (pintype "passive"))
      (node (ref "X6") (pin "1") (pinfunction "KL_1") (pintype "passive"))
    )
    (net (code "78") (name "unconnected-(U$2-PadSWOPEN)") (class "Default")
      (node (ref "U$2") (pin "SWOPEN") (pinfunction "SWOPEN_SWOPEN") (pintype "bidirectional"))
    )
    (net (code "79") (name "unconnected-(U$3-PadSWOPEN)") (class "Default")
      (node (ref "U$3") (pin "SWOPEN") (pinfunction "SWOPEN_SWOPEN") (pintype "bidirectional"))
    )
    (net (code "80") (name "unconnected-(U$4-PadSWOPEN)") (class "Default")
      (node (ref "U$4") (pin "SWOPEN") (pinfunction "SWOPEN_SWOPEN") (pintype "bidirectional"))
    )
    (net (code "81") (name "unconnected-(U$5-PadSWOPEN)") (class "Default")
      (node (ref "U$5") (pin "SWOPEN") (pinfunction "SWOPEN_SWOPEN") (pintype "bidirectional"))
    )
    (net (code "82") (name "unconnected-(U$6-PadS)") (class "Default")
      (node (ref "U$6") (pin "S") (pinfunction "S_S") (pintype "passive"))
    )
  )
)
